# POWERMANAGE.net
KiCad netlist of a schematic drawn in Altium Designer
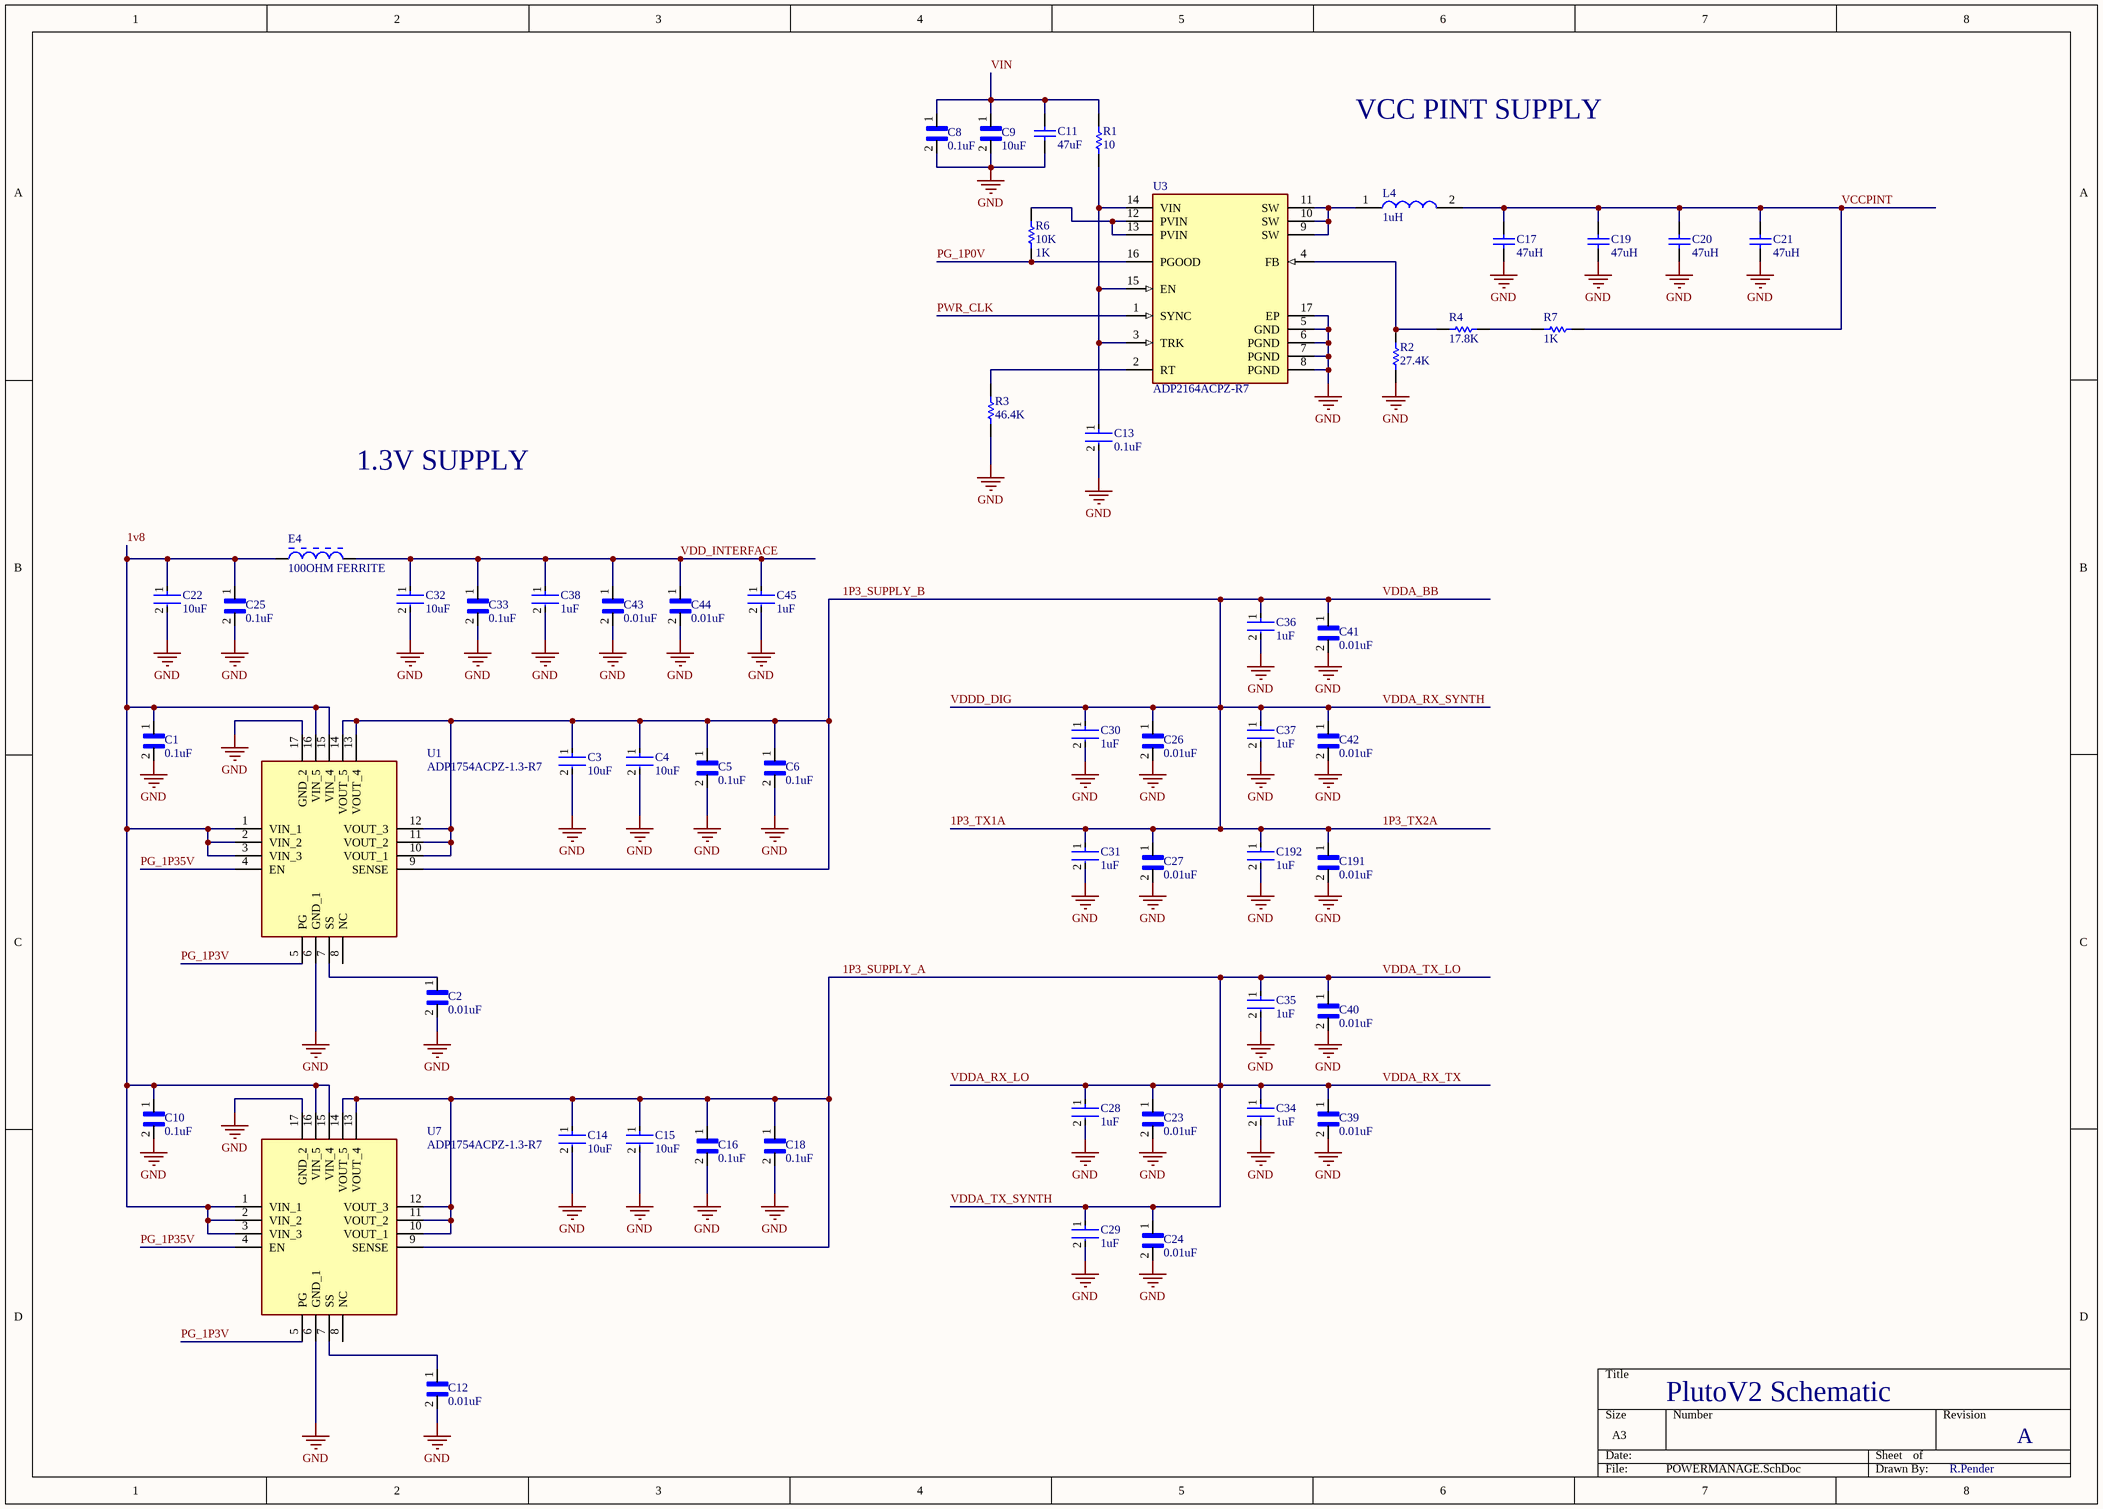
[diagram p0: POWERMANAGE.SchDoc]

(export (version "E")
  (design (tool "Eeschema 10.0.6"))
  (components
    (comp (ref "C1")
      (value "0.1uF")
      (footprint "CAPC0603X33N")
      (description "CAP 0.1UF 16VDC X5R 20% SMD 0201 PAPER TAPE")
      (fields (field (name "MP") "GRM033R61C104ME84D"))
      (libsource (lib "GRM033R61C104ME84D") (part "GRM033R61C104ME84D"))
    )
    (comp (ref "C2")
      (value "0.01uF")
      (footprint "CAPC0603X33N")
      (description "SMD Capacitor X7R(EIA) with Capacitance: 10000pF Tol. 10%. Rated Voltage: 10Vdc")
      (fields (field (name "MP") "GRM033R71A103KA01D") (field (name "MF") "Murata"))
      (libsource (lib "GRM033R71A103KA01D") (part "GRM033R71A103KA01D"))
    )
    (comp (ref "C3")
      (value "10uF")
      (footprint "FP-GRM188-0_1-e0_2_0_55-IPC_C")
      (description "Chip Multilayer Ceramic Capacitors for General Purpose, 0603, 10uF, X5R, 15%, 20%, 6.3V")
      (fields (field (name "VOLTAGE") "6.3V") (field (name "TOLERANCE") "20%"))
      (libsource (lib "Altium Content Vault") (part "02cd4be3c70576c341d710602a673aa"))
    )
    (comp (ref "C4")
      (value "10uF")
      (footprint "FP-GRM188-0_1-e0_2_0_55-IPC_C")
      (description "Chip Multilayer Ceramic Capacitors for General Purpose, 0603, 10uF, X5R, 15%, 20%, 6.3V")
      (fields (field (name "VOLTAGE") "6.3V") (field (name "TOLERANCE") "20%"))
      (libsource (lib "Altium Content Vault") (part "02cd4be3c70576c341d710602a673aa"))
    )
    (comp (ref "C5")
      (value "0.1uF")
      (footprint "CAPC0603X33N")
      (description "CAP 0.1UF 16VDC X5R 20% SMD 0201 PAPER TAPE")
      (fields (field (name "MP") "GRM033R61C104ME84D"))
      (libsource (lib "GRM033R61C104ME84D") (part "GRM033R61C104ME84D"))
    )
    (comp (ref "C6")
      (value "0.1uF")
      (footprint "CAPC0603X33N")
      (description "CAP 0.1UF 16VDC X5R 20% SMD 0201 PAPER TAPE")
      (fields (field (name "MP") "GRM033R61C104ME84D"))
      (libsource (lib "GRM033R61C104ME84D") (part "GRM033R61C104ME84D"))
    )
    (comp (ref "C8")
      (value "0.1uF")
      (footprint "CAPC0603X33N")
      (description "CAP 0.1UF 16VDC X5R 20% SMD 0201 PAPER TAPE")
      (fields (field (name "MP") "GRM033R61C104ME84D"))
      (libsource (lib "GRM033R61C104ME84D") (part "GRM033R61C104ME84D"))
    )
    (comp (ref "C9")
      (value "10uF")
      (footprint "CAPC0603X33N")
      (description "SMD Capacitor X7R(EIA) with Capacitance: 10000pF Tol. 10%. Rated Voltage: 10Vdc")
      (fields (field (name "MP") "GRM033R71A103KA01D") (field (name "MF") "Murata"))
      (libsource (lib "GRM033R71A103KA01D") (part "GRM033R71A103KA01D"))
    )
    (comp (ref "C10")
      (value "0.1uF")
      (footprint "CAPC0603X33N")
      (description "CAP 0.1UF 16VDC X5R 20% SMD 0201 PAPER TAPE")
      (fields (field (name "MP") "GRM033R61C104ME84D"))
      (libsource (lib "GRM033R61C104ME84D") (part "GRM033R61C104ME84D"))
    )
    (comp (ref "C11")
      (value "47uF")
      (footprint "TAYO-JMK212BBJ476MG-T_L")
      (fields
        (field (name "MANUFACTURER") "Taiyo Yuden")
        (field (name "TOLERANCE") "±20%")
        (field (name "PCN PART NUMBER") "X5R,X7RDielectrics23/Jan/2008")
      )
      (libsource (lib "Altium Content Vault") (part "CAP-NP-2"))
    )
    (comp (ref "C12")
      (value "0.01uF")
      (footprint "CAPC0603X33N")
      (description "SMD Capacitor X7R(EIA) with Capacitance: 10000pF Tol. 10%. Rated Voltage: 10Vdc")
      (fields (field (name "MP") "GRM033R71A103KA01D") (field (name "MF") "Murata"))
      (libsource (lib "GRM033R71A103KA01D") (part "GRM033R71A103KA01D"))
    )
    (comp (ref "C13")
      (value "0.1uF")
      (footprint "FP-GRM188-0_15-MFG")
      (description "Chip Multilayer Ceramic Capacitors for General Purpose, 0603, 10uF, X5R, 15%, 20%, 10V")
      (fields (field (name "TOLERANCE") "20%"))
      (libsource (lib "Altium Content Vault") (part "02cd4be3c70576c341d710602a673aa"))
    )
    (comp (ref "C14")
      (value "10uF")
      (footprint "FP-GRM188-0_1-e0_2_0_55-IPC_C")
      (description "Chip Multilayer Ceramic Capacitors for General Purpose, 0603, 10uF, X5R, 15%, 20%, 6.3V")
      (fields (field (name "VOLTAGE") "6.3V") (field (name "TOLERANCE") "20%"))
      (libsource (lib "Altium Content Vault") (part "02cd4be3c70576c341d710602a673aa"))
    )
    (comp (ref "C15")
      (value "10uF")
      (footprint "FP-GRM188-0_1-e0_2_0_55-IPC_C")
      (description "Chip Multilayer Ceramic Capacitors for General Purpose, 0603, 10uF, X5R, 15%, 20%, 6.3V")
      (fields (field (name "VOLTAGE") "6.3V") (field (name "TOLERANCE") "20%"))
      (libsource (lib "Altium Content Vault") (part "02cd4be3c70576c341d710602a673aa"))
    )
    (comp (ref "C16")
      (value "0.1uF")
      (footprint "CAPC0603X33N")
      (description "CAP 0.1UF 16VDC X5R 20% SMD 0201 PAPER TAPE")
      (fields (field (name "MP") "GRM033R61C104ME84D"))
      (libsource (lib "GRM033R61C104ME84D") (part "GRM033R61C104ME84D"))
    )
    (comp (ref "C17")
      (value "47uH")
      (footprint "TAYO-JMK212BBJ476MG-T_L")
      (fields
        (field (name "MANUFACTURER") "Taiyo Yuden")
        (field (name "TOLERANCE") "±20%")
        (field (name "PCN PART NUMBER") "X5R,X7RDielectrics23/Jan/2008")
      )
      (libsource (lib "Altium Content Vault") (part "CAP-NP-2"))
    )
    (comp (ref "C18")
      (value "0.1uF")
      (footprint "CAPC0603X33N")
      (description "CAP 0.1UF 16VDC X5R 20% SMD 0201 PAPER TAPE")
      (fields (field (name "MP") "GRM033R61C104ME84D"))
      (libsource (lib "GRM033R61C104ME84D") (part "GRM033R61C104ME84D"))
    )
    (comp (ref "C19")
      (value "47uH")
      (footprint "TAYO-JMK212BBJ476MG-T_L")
      (fields
        (field (name "MANUFACTURER") "Taiyo Yuden")
        (field (name "TOLERANCE") "±20%")
        (field (name "PCN PART NUMBER") "X5R,X7RDielectrics23/Jan/2008")
      )
      (libsource (lib "Altium Content Vault") (part "CAP-NP-2"))
    )
    (comp (ref "C20")
      (value "47uH")
      (footprint "TAYO-JMK212BBJ476MG-T_L")
      (fields
        (field (name "MANUFACTURER") "Taiyo Yuden")
        (field (name "TOLERANCE") "±20%")
        (field (name "PCN PART NUMBER") "X5R,X7RDielectrics23/Jan/2008")
      )
      (libsource (lib "Altium Content Vault") (part "CAP-NP-2"))
    )
    (comp (ref "C21")
      (value "47uH")
      (footprint "TAYO-JMK212BBJ476MG-T_L")
      (fields
        (field (name "MANUFACTURER") "Taiyo Yuden")
        (field (name "TOLERANCE") "±20%")
        (field (name "PCN PART NUMBER") "X5R,X7RDielectrics23/Jan/2008")
      )
      (libsource (lib "Altium Content Vault") (part "CAP-NP-2"))
    )
    (comp (ref "C22")
      (value "10uF")
      (footprint "FP-GRM188-0_1-e0_2_0_55-IPC_C")
      (description "Chip Multilayer Ceramic Capacitors for General Purpose, 0603, 10uF, X5R, 15%, 20%, 6.3V")
      (fields (field (name "VOLTAGE") "6.3V") (field (name "TOLERANCE") "20%"))
      (libsource (lib "Altium Content Vault") (part "02cd4be3c70576c341d710602a673aa"))
    )
    (comp (ref "C23")
      (value "0.01uF")
      (footprint "CAPC0603X33N")
      (description "SMD Capacitor X7R(EIA) with Capacitance: 10000pF Tol. 10%. Rated Voltage: 10Vdc")
      (fields (field (name "MP") "GRM033R71A103KA01D") (field (name "MF") "Murata"))
      (libsource (lib "GRM033R71A103KA01D") (part "GRM033R71A103KA01D"))
    )
    (comp (ref "C24")
      (value "0.01uF")
      (footprint "CAPC0603X33N")
      (description "SMD Capacitor X7R(EIA) with Capacitance: 10000pF Tol. 10%. Rated Voltage: 10Vdc")
      (fields (field (name "MP") "GRM033R71A103KA01D") (field (name "MF") "Murata"))
      (libsource (lib "GRM033R71A103KA01D") (part "GRM033R71A103KA01D"))
    )
    (comp (ref "C25")
      (value "0.1uF")
      (footprint "CAPC0603X33N")
      (description "CAP 0.1UF 16VDC X5R 20% SMD 0201 PAPER TAPE")
      (fields (field (name "MP") "GRM033R61C104ME84D"))
      (libsource (lib "GRM033R61C104ME84D") (part "GRM033R61C104ME84D"))
    )
    (comp (ref "C26")
      (value "0.01uF")
      (footprint "CAPC0603X33N")
      (description "SMD Capacitor X7R(EIA) with Capacitance: 10000pF Tol. 10%. Rated Voltage: 10Vdc")
      (fields (field (name "MP") "GRM033R71A103KA01D") (field (name "MF") "Murata"))
      (libsource (lib "GRM033R71A103KA01D") (part "GRM033R71A103KA01D"))
    )
    (comp (ref "C27")
      (value "0.01uF")
      (footprint "CAPC0603X33N")
      (description "SMD Capacitor X7R(EIA) with Capacitance: 10000pF Tol. 10%. Rated Voltage: 10Vdc")
      (fields (field (name "MP") "GRM033R71A103KA01D") (field (name "MF") "Murata"))
      (libsource (lib "GRM033R71A103KA01D") (part "GRM033R71A103KA01D"))
    )
    (comp (ref "C28")
      (value "1uF")
      (footprint "FP-0402-L_1_0_0_05-W_0_5-IPC_B")
      (description "None")
      (fields (field (name "TOLERANCE") "10%"))
      (libsource (lib "Altium Content Vault") (part "b4654b650e69147ec39a6b967a45e02"))
    )
    (comp (ref "C29")
      (value "1uF")
      (footprint "FP-0402-L_1_0_0_05-W_0_5-IPC_B")
      (description "None")
      (fields (field (name "TOLERANCE") "10%"))
      (libsource (lib "Altium Content Vault") (part "b4654b650e69147ec39a6b967a45e02"))
    )
    (comp (ref "C30")
      (value "1uF")
      (footprint "FP-0402-L_1_0_0_05-W_0_5-IPC_B")
      (description "None")
      (fields (field (name "TOLERANCE") "10%"))
      (libsource (lib "Altium Content Vault") (part "b4654b650e69147ec39a6b967a45e02"))
    )
    (comp (ref "C31")
      (value "1uF")
      (footprint "FP-0402-L_1_0_0_05-W_0_5-IPC_B")
      (description "None")
      (fields (field (name "TOLERANCE") "10%"))
      (libsource (lib "Altium Content Vault") (part "b4654b650e69147ec39a6b967a45e02"))
    )
    (comp (ref "C32")
      (value "10uF")
      (footprint "FP-GRM188-0_1-e0_2_0_55-IPC_C")
      (description "Chip Multilayer Ceramic Capacitors for General Purpose, 0603, 10uF, X5R, 15%, 20%, 6.3V")
      (fields (field (name "VOLTAGE") "6.3V") (field (name "TOLERANCE") "20%"))
      (libsource (lib "Altium Content Vault") (part "02cd4be3c70576c341d710602a673aa"))
    )
    (comp (ref "C33")
      (value "0.1uF")
      (footprint "CAPC0603X33N")
      (description "CAP 0.1UF 16VDC X5R 20% SMD 0201 PAPER TAPE")
      (fields (field (name "MP") "GRM033R61C104ME84D"))
      (libsource (lib "GRM033R61C104ME84D") (part "GRM033R61C104ME84D"))
    )
    (comp (ref "C34")
      (value "1uF")
      (footprint "FP-0402-L_1_0_0_05-W_0_5-IPC_B")
      (description "None")
      (fields (field (name "TOLERANCE") "10%"))
      (libsource (lib "Altium Content Vault") (part "b4654b650e69147ec39a6b967a45e02"))
    )
    (comp (ref "C35")
      (value "1uF")
      (footprint "FP-0402-L_1_0_0_05-W_0_5-IPC_B")
      (description "None")
      (fields (field (name "TOLERANCE") "10%"))
      (libsource (lib "Altium Content Vault") (part "b4654b650e69147ec39a6b967a45e02"))
    )
    (comp (ref "C36")
      (value "1uF")
      (footprint "FP-0402-L_1_0_0_05-W_0_5-IPC_B")
      (description "None")
      (fields (field (name "TOLERANCE") "10%"))
      (libsource (lib "Altium Content Vault") (part "b4654b650e69147ec39a6b967a45e02"))
    )
    (comp (ref "C37")
      (value "1uF")
      (footprint "FP-0402-L_1_0_0_05-W_0_5-IPC_B")
      (description "None")
      (fields (field (name "TOLERANCE") "10%"))
      (libsource (lib "Altium Content Vault") (part "b4654b650e69147ec39a6b967a45e02"))
    )
    (comp (ref "C38")
      (value "1uF")
      (footprint "FP-0402-L_1_0_0_05-W_0_5-IPC_A")
      (description "None")
      (fields (field (name "TOLERANCE") "10%"))
      (libsource (lib "Altium Content Vault") (part "b4654b650e69147ec39a6b967a45e02"))
    )
    (comp (ref "C39")
      (value "0.01uF")
      (footprint "CAPC0603X33N")
      (description "SMD Capacitor X7R(EIA) with Capacitance: 10000pF Tol. 10%. Rated Voltage: 10Vdc")
      (fields (field (name "MP") "GRM033R71A103KA01D") (field (name "MF") "Murata"))
      (libsource (lib "GRM033R71A103KA01D") (part "GRM033R71A103KA01D"))
    )
    (comp (ref "C40")
      (value "0.01uF")
      (footprint "CAPC0603X33N")
      (description "SMD Capacitor X7R(EIA) with Capacitance: 10000pF Tol. 10%. Rated Voltage: 10Vdc")
      (fields (field (name "MP") "GRM033R71A103KA01D") (field (name "MF") "Murata"))
      (libsource (lib "GRM033R71A103KA01D") (part "GRM033R71A103KA01D"))
    )
    (comp (ref "C41")
      (value "0.01uF")
      (footprint "CAPC0603X33N")
      (description "SMD Capacitor X7R(EIA) with Capacitance: 10000pF Tol. 10%. Rated Voltage: 10Vdc")
      (fields (field (name "MP") "GRM033R71A103KA01D") (field (name "MF") "Murata"))
      (libsource (lib "GRM033R71A103KA01D") (part "GRM033R71A103KA01D"))
    )
    (comp (ref "C42")
      (value "0.01uF")
      (footprint "CAPC0603X33N")
      (description "SMD Capacitor X7R(EIA) with Capacitance: 10000pF Tol. 10%. Rated Voltage: 10Vdc")
      (fields (field (name "MP") "GRM033R71A103KA01D") (field (name "MF") "Murata"))
      (libsource (lib "GRM033R71A103KA01D") (part "GRM033R71A103KA01D"))
    )
    (comp (ref "C43")
      (value "0.01uF")
      (footprint "CAPC0603X33N")
      (description "SMD Capacitor X7R(EIA) with Capacitance: 10000pF Tol. 10%. Rated Voltage: 10Vdc")
      (fields (field (name "MP") "GRM033R71A103KA01D") (field (name "MF") "Murata"))
      (libsource (lib "GRM033R71A103KA01D") (part "GRM033R71A103KA01D"))
    )
    (comp (ref "C44")
      (value "0.01uF")
      (footprint "CAPC0603X33N")
      (description "SMD Capacitor X7R(EIA) with Capacitance: 10000pF Tol. 10%. Rated Voltage: 10Vdc")
      (fields (field (name "MP") "GRM033R71A103KA01D") (field (name "MF") "Murata"))
      (libsource (lib "GRM033R71A103KA01D") (part "GRM033R71A103KA01D"))
    )
    (comp (ref "C45")
      (value "1uF")
      (footprint "FP-0402-L_1_0_0_05-W_0_5-IPC_A")
      (description "None")
      (fields (field (name "TOLERANCE") "10%"))
      (libsource (lib "Altium Content Vault") (part "b4654b650e69147ec39a6b967a45e02"))
    )
    (comp (ref "C191")
      (value "0.01uF")
      (footprint "CAPC0603X33N")
      (description "SMD Capacitor X7R(EIA) with Capacitance: 10000pF Tol. 10%. Rated Voltage: 10Vdc")
      (fields (field (name "MP") "GRM033R71A103KA01D") (field (name "MF") "Murata"))
      (libsource (lib "GRM033R71A103KA01D") (part "GRM033R71A103KA01D"))
    )
    (comp (ref "C192")
      (value "1uF")
      (footprint "FP-0402-L_1_0_0_05-W_0_5-IPC_B")
      (description "None")
      (fields (field (name "TOLERANCE") "10%"))
      (libsource (lib "Altium Content Vault") (part "b4654b650e69147ec39a6b967a45e02"))
    )
    (comp (ref "E4")
      (value "100OHM FERRITE")
      (footprint "TDK-MPZ2012S101A-2_V")
      (fields (field (name "TOLERANCE") "25%") (field (name "MANUFACTURER") "TDK"))
      (libsource (lib "Altium Content Vault") (part "BEAD-2"))
    )
    (comp (ref "L4")
      (value "1uH")
      (footprint "SamacSys:XFL4020102MEB")
      (description "Inductor")
      (fields (field (name "MANUFACTURER_PART_NUMBER") "XFL4020-102MEB"))
      (libsource (lib "*") (part "XFL4020-102MEB"))
    )
    (comp (ref "R1")
      (value "10")
      (footprint "RESC0603X26X15LL03T05")
      (fields (field (name "MANUFACTURER") "Panasonic") (field (name "PART NUMBER") "ERJ1GNF10R0C"))
      (libsource (lib "Altium Content Vault") (part "RES"))
    )
    (comp (ref "R2")
      (value "27.4K")
      (footprint "2-0402")
      (fields (field (name "PUBLISHER") "Altium Limited"))
      (libsource (lib "Panasonic Resistor") (part "ERJ2RK"))
    )
    (comp (ref "R3")
      (value "46.4K")
      (footprint "1-0201")
      (description "Thick Film Chip Resistor, 10 Ohm to 1M Ohm Range, 5% Tolerance, 0201 Size, 0.05 W")
      (fields (field (name "PUBLISHER") "Altium Limited"))
      (libsource (lib "Panasonic Resistor") (part "ERJ1GE"))
    )
    (comp (ref "R4")
      (value "17.8K")
      (footprint "2-0402")
      (fields (field (name "PUBLISHER") "Altium Limited"))
      (libsource (lib "Panasonic Resistor") (part "ERJ2RK"))
    )
    (comp (ref "R6")
      (value "10K")
      (footprint "RESC1005X35N")
      (description "Resistor")
      (fields (field (name "ALTIUM_VALUE") "1K") (field (name "PUBLISHER") "Altium Limited"))
      (libsource (lib "Miscellaneous Devices") (part "Res1"))
    )
    (comp (ref "R7")
      (value "1K")
      (footprint "2-0402")
      (fields (field (name "PUBLISHER") "Altium Limited"))
      (libsource (lib "Panasonic Resistor") (part "ERJ2RK"))
    )
    (comp (ref "U1")
      (value "ADP1754ACPZ-1.3-R7")
      (footprint "SamacSys:QFN65P400X400X80-17N-D")
      (description "Integrated Circuit")
      (libsource (lib "*") (part "ADP1754ACPZ-1.3-R7"))
    )
    (comp (ref "U3")
      (value "ADP2164ACPZ-R7")
      (footprint "FP-CP-16-26-IPC_C")
      (description "Buck Switching Regulator IC Positive Adjustable 0.6V 1 Output 4A 16-WQFN Exposed Pad, CSP")
      (fields (field (name "MANUFACTURER") "Analog Devices"))
      (libsource (lib "Altium Content Vault") (part "77e3d03b05ecb97249e3a8385dd6fb0"))
    )
    (comp (ref "U7")
      (value "ADP1754ACPZ-1.3-R7")
      (footprint "SamacSys:QFN65P400X400X80-17N-D")
      (description "Integrated Circuit")
      (libsource (lib "*") (part "ADP1754ACPZ-1.3-R7"))
    )
  )
  (nets
    (net (code "1") (name "/1P3_SUPPLY_A") (class "Default")
      (node (ref "C14") (pin "1") (pinfunction "1_1") (pintype "passive"))
      (node (ref "C15") (pin "1") (pinfunction "1_1") (pintype "passive"))
      (node (ref "C16") (pin "1") (pinfunction "1_1") (pintype "passive"))
      (node (ref "C18") (pin "1") (pinfunction "1_1") (pintype "passive"))
      (node (ref "C23") (pin "1") (pinfunction "1_1") (pintype "passive"))
      (node (ref "C24") (pin "1") (pinfunction "1_1") (pintype "passive"))
      (node (ref "C28") (pin "1") (pinfunction "1_1") (pintype "passive"))
      (node (ref "C29") (pin "1") (pinfunction "1_1") (pintype "passive"))
      (node (ref "C34") (pin "1") (pinfunction "1_1") (pintype "passive"))
      (node (ref "C35") (pin "1") (pinfunction "1_1") (pintype "passive"))
      (node (ref "C39") (pin "1") (pinfunction "1_1") (pintype "passive"))
      (node (ref "C40") (pin "1") (pinfunction "1_1") (pintype "passive"))
      (node (ref "U7") (pin "10") (pinfunction "VOUT_1_10") (pintype "passive"))
      (node (ref "U7") (pin "11") (pinfunction "VOUT_2_11") (pintype "passive"))
      (node (ref "U7") (pin "12") (pinfunction "VOUT_3_12") (pintype "passive"))
      (node (ref "U7") (pin "13") (pinfunction "VOUT_4_13") (pintype "passive"))
      (node (ref "U7") (pin "14") (pinfunction "VOUT_5_14") (pintype "passive"))
      (node (ref "U7") (pin "9") (pinfunction "SENSE_9") (pintype "passive"))
    )
    (net (code "2") (name "/1P3_SUPPLY_B") (class "Default")
      (node (ref "C191") (pin "1") (pinfunction "1_1") (pintype "passive"))
      (node (ref "C192") (pin "1") (pinfunction "1_1") (pintype "passive"))
      (node (ref "C26") (pin "1") (pinfunction "1_1") (pintype "passive"))
      (node (ref "C27") (pin "1") (pinfunction "1_1") (pintype "passive"))
      (node (ref "C3") (pin "1") (pinfunction "1_1") (pintype "passive"))
      (node (ref "C30") (pin "1") (pinfunction "1_1") (pintype "passive"))
      (node (ref "C31") (pin "1") (pinfunction "1_1") (pintype "passive"))
      (node (ref "C36") (pin "1") (pinfunction "1_1") (pintype "passive"))
      (node (ref "C37") (pin "1") (pinfunction "1_1") (pintype "passive"))
      (node (ref "C4") (pin "1") (pinfunction "1_1") (pintype "passive"))
      (node (ref "C41") (pin "1") (pinfunction "1_1") (pintype "passive"))
      (node (ref "C42") (pin "1") (pinfunction "1_1") (pintype "passive"))
      (node (ref "C5") (pin "1") (pinfunction "1_1") (pintype "passive"))
      (node (ref "C6") (pin "1") (pinfunction "1_1") (pintype "passive"))
      (node (ref "U1") (pin "10") (pinfunction "VOUT_1_10") (pintype "passive"))
      (node (ref "U1") (pin "11") (pinfunction "VOUT_2_11") (pintype "passive"))
      (node (ref "U1") (pin "12") (pinfunction "VOUT_3_12") (pintype "passive"))
      (node (ref "U1") (pin "13") (pinfunction "VOUT_4_13") (pintype "passive"))
      (node (ref "U1") (pin "14") (pinfunction "VOUT_5_14") (pintype "passive"))
      (node (ref "U1") (pin "9") (pinfunction "SENSE_9") (pintype "passive"))
    )
    (net (code "3") (name "/1v8") (class "Default")
      (node (ref "C1") (pin "1") (pinfunction "1_1") (pintype "passive"))
      (node (ref "C10") (pin "1") (pinfunction "1_1") (pintype "passive"))
      (node (ref "C22") (pin "1") (pinfunction "1_1") (pintype "passive"))
      (node (ref "C25") (pin "1") (pinfunction "1_1") (pintype "passive"))
      (node (ref "E4") (pin "1") (pinfunction "1_1") (pintype "passive"))
      (node (ref "U1") (pin "1") (pinfunction "VIN_1_1") (pintype "passive"))
      (node (ref "U1") (pin "15") (pinfunction "VIN_4_15") (pintype "passive"))
      (node (ref "U1") (pin "16") (pinfunction "VIN_5_16") (pintype "passive"))
      (node (ref "U1") (pin "2") (pinfunction "VIN_2_2") (pintype "passive"))
      (node (ref "U1") (pin "3") (pinfunction "VIN_3_3") (pintype "passive"))
      (node (ref "U7") (pin "1") (pinfunction "VIN_1_1") (pintype "passive"))
      (node (ref "U7") (pin "15") (pinfunction "VIN_4_15") (pintype "passive"))
      (node (ref "U7") (pin "16") (pinfunction "VIN_5_16") (pintype "passive"))
      (node (ref "U7") (pin "2") (pinfunction "VIN_2_2") (pintype "passive"))
      (node (ref "U7") (pin "3") (pinfunction "VIN_3_3") (pintype "passive"))
    )
    (net (code "4") (name "/PG_1P0V") (class "Default")
      (node (ref "R6") (pin "1") (pinfunction "1_1") (pintype "passive"))
      (node (ref "U3") (pin "16") (pinfunction "PGOOD_16") (pintype "open_collector"))
    )
    (net (code "5") (name "/PG_1P3V") (class "Default")
      (node (ref "U1") (pin "5") (pinfunction "PG_5") (pintype "passive"))
      (node (ref "U7") (pin "5") (pinfunction "PG_5") (pintype "passive"))
    )
    (net (code "6") (name "/PG_1P35V") (class "Default")
      (node (ref "U1") (pin "4") (pinfunction "EN_4") (pintype "passive"))
      (node (ref "U7") (pin "4") (pinfunction "EN_4") (pintype "passive"))
    )
    (net (code "7") (name "/PWR_CLK") (class "Default")
      (node (ref "U3") (pin "1") (pinfunction "SYNC_1") (pintype "input"))
    )
    (net (code "8") (name "/VCCPINT") (class "Default")
      (node (ref "C17") (pin "1") (pinfunction "1_1") (pintype "passive"))
      (node (ref "C19") (pin "1") (pinfunction "1_1") (pintype "passive"))
      (node (ref "C20") (pin "1") (pinfunction "1_1") (pintype "passive"))
      (node (ref "C21") (pin "1") (pinfunction "1_1") (pintype "passive"))
      (node (ref "L4") (pin "2") (pinfunction "2_2") (pintype "passive"))
      (node (ref "R7") (pin "2") (pinfunction "2_2") (pintype "passive"))
    )
    (net (code "9") (name "/VDD_INTERFACE") (class "Default")
      (node (ref "C32") (pin "1") (pinfunction "1_1") (pintype "passive"))
      (node (ref "C33") (pin "1") (pinfunction "1_1") (pintype "passive"))
      (node (ref "C38") (pin "1") (pinfunction "1_1") (pintype "passive"))
      (node (ref "C43") (pin "1") (pinfunction "1_1") (pintype "passive"))
      (node (ref "C44") (pin "1") (pinfunction "1_1") (pintype "passive"))
      (node (ref "C45") (pin "1") (pinfunction "1_1") (pintype "passive"))
      (node (ref "E4") (pin "2") (pinfunction "2_2") (pintype "passive"))
    )
    (net (code "10") (name "/VIN") (class "Default")
      (node (ref "C11") (pin "1") (pinfunction "1_1") (pintype "passive"))
      (node (ref "C8") (pin "1") (pinfunction "1_1") (pintype "passive"))
      (node (ref "C9") (pin "1") (pinfunction "1_1") (pintype "passive"))
      (node (ref "R1") (pin "2") (pinfunction "2_2") (pintype "passive"))
    )
    (net (code "11") (name "GND") (class "Default")
      (node (ref "C1") (pin "2") (pinfunction "2_2") (pintype "passive"))
      (node (ref "C10") (pin "2") (pinfunction "2_2") (pintype "passive"))
      (node (ref "C11") (pin "2") (pinfunction "2_2") (pintype "passive"))
      (node (ref "C12") (pin "2") (pinfunction "2_2") (pintype "passive"))
      (node (ref "C13") (pin "2") (pinfunction "2_2") (pintype "passive"))
      (node (ref "C14") (pin "2") (pinfunction "2_2") (pintype "passive"))
      (node (ref "C15") (pin "2") (pinfunction "2_2") (pintype "passive"))
      (node (ref "C16") (pin "2") (pinfunction "2_2") (pintype "passive"))
      (node (ref "C17") (pin "2") (pinfunction "2_2") (pintype "passive"))
      (node (ref "C18") (pin "2") (pinfunction "2_2") (pintype "passive"))
      (node (ref "C19") (pin "2") (pinfunction "2_2") (pintype "passive"))
      (node (ref "C191") (pin "2") (pinfunction "2_2") (pintype "passive"))
      (node (ref "C192") (pin "2") (pinfunction "2_2") (pintype "passive"))
      (node (ref "C2") (pin "2") (pinfunction "2_2") (pintype "passive"))
      (node (ref "C20") (pin "2") (pinfunction "2_2") (pintype "passive"))
      (node (ref "C21") (pin "2") (pinfunction "2_2") (pintype "passive"))
      (node (ref "C22") (pin "2") (pinfunction "2_2") (pintype "passive"))
      (node (ref "C23") (pin "2") (pinfunction "2_2") (pintype "passive"))
      (node (ref "C24") (pin "2") (pinfunction "2_2") (pintype "passive"))
      (node (ref "C25") (pin "2") (pinfunction "2_2") (pintype "passive"))
      (node (ref "C26") (pin "2") (pinfunction "2_2") (pintype "passive"))
      (node (ref "C27") (pin "2") (pinfunction "2_2") (pintype "passive"))
      (node (ref "C28") (pin "2") (pinfunction "2_2") (pintype "passive"))
      (node (ref "C29") (pin "2") (pinfunction "2_2") (pintype "passive"))
      (node (ref "C3") (pin "2") (pinfunction "2_2") (pintype "passive"))
      (node (ref "C30") (pin "2") (pinfunction "2_2") (pintype "passive"))
      (node (ref "C31") (pin "2") (pinfunction "2_2") (pintype "passive"))
      (node (ref "C32") (pin "2") (pinfunction "2_2") (pintype "passive"))
      (node (ref "C33") (pin "2") (pinfunction "2_2") (pintype "passive"))
      (node (ref "C34") (pin "2") (pinfunction "2_2") (pintype "passive"))
      (node (ref "C35") (pin "2") (pinfunction "2_2") (pintype "passive"))
      (node (ref "C36") (pin "2") (pinfunction "2_2") (pintype "passive"))
      (node (ref "C37") (pin "2") (pinfunction "2_2") (pintype "passive"))
      (node (ref "C38") (pin "2") (pinfunction "2_2") (pintype "passive"))
      (node (ref "C39") (pin "2") (pinfunction "2_2") (pintype "passive"))
      (node (ref "C4") (pin "2") (pinfunction "2_2") (pintype "passive"))
      (node (ref "C40") (pin "2") (pinfunction "2_2") (pintype "passive"))
      (node (ref "C41") (pin "2") (pinfunction "2_2") (pintype "passive"))
      (node (ref "C42") (pin "2") (pinfunction "2_2") (pintype "passive"))
      (node (ref "C43") (pin "2") (pinfunction "2_2") (pintype "passive"))
      (node (ref "C44") (pin "2") (pinfunction "2_2") (pintype "passive"))
      (node (ref "C45") (pin "2") (pinfunction "2_2") (pintype "passive"))
      (node (ref "C5") (pin "2") (pinfunction "2_2") (pintype "passive"))
      (node (ref "C6") (pin "2") (pinfunction "2_2") (pintype "passive"))
      (node (ref "C8") (pin "2") (pinfunction "2_2") (pintype "passive"))
      (node (ref "C9") (pin "2") (pinfunction "2_2") (pintype "passive"))
      (node (ref "R2") (pin "2") (pinfunction "2_2") (pintype "passive"))
      (node (ref "R3") (pin "2") (pinfunction "2_2") (pintype "passive"))
      (node (ref "U1") (pin "17") (pinfunction "GND_2_17") (pintype "passive"))
      (node (ref "U1") (pin "6") (pinfunction "GND_1_6") (pintype "passive"))
      (node (ref "U3") (pin "17") (pinfunction "EP_17") (pintype "power_in"))
      (node (ref "U3") (pin "5") (pinfunction "GND_5") (pintype "power_in"))
      (node (ref "U3") (pin "6") (pinfunction "PGND_6") (pintype "power_in"))
      (node (ref "U3") (pin "7") (pinfunction "PGND_7") (pintype "power_in"))
      (node (ref "U3") (pin "8") (pinfunction "PGND_8") (pintype "power_in"))
      (node (ref "U7") (pin "17") (pinfunction "GND_2_17") (pintype "passive"))
      (node (ref "U7") (pin "6") (pinfunction "GND_1_6") (pintype "passive"))
    )
    (net (code "12") (name "Net-(L4-Pad1)") (class "Default")
      (node (ref "L4") (pin "1") (pinfunction "1_1") (pintype "passive"))
      (node (ref "U3") (pin "10") (pinfunction "SW_10") (pintype "power_in"))
      (node (ref "U3") (pin "11") (pinfunction "SW_11") (pintype "power_in"))
      (node (ref "U3") (pin "9") (pinfunction "SW_9") (pintype "power_in"))
    )
    (net (code "13") (name "Net-(R4-Pad2)") (class "Default")
      (node (ref "R4") (pin "2") (pinfunction "2_2") (pintype "passive"))
      (node (ref "R7") (pin "1") (pinfunction "1_1") (pintype "passive"))
    )
    (net (code "14") (name "Net-(R6-Pad2)") (class "Default")
      (node (ref "R6") (pin "2") (pinfunction "2_2") (pintype "passive"))
      (node (ref "U3") (pin "12") (pinfunction "PVIN_12") (pintype "power_in"))
      (node (ref "U3") (pin "13") (pinfunction "PVIN_13") (pintype "power_in"))
    )
    (net (code "15") (name "Net-(U1-SS)") (class "Default")
      (node (ref "C2") (pin "1") (pinfunction "1_1") (pintype "passive"))
      (node (ref "U1") (pin "7") (pinfunction "SS_7") (pintype "passive"))
    )
    (net (code "16") (name "Net-(U3-EN)") (class "Default")
      (node (ref "C13") (pin "1") (pinfunction "1_1") (pintype "passive"))
      (node (ref "R1") (pin "1") (pinfunction "1_1") (pintype "passive"))
      (node (ref "U3") (pin "14") (pinfunction "VIN_14") (pintype "power_in"))
      (node (ref "U3") (pin "15") (pinfunction "EN_15") (pintype "input"))
      (node (ref "U3") (pin "3") (pinfunction "TRK_3") (pintype "input"))
    )
    (net (code "17") (name "Net-(U3-FB)") (class "Default")
      (node (ref "R2") (pin "1") (pinfunction "1_1") (pintype "passive"))
      (node (ref "R4") (pin "1") (pinfunction "1_1") (pintype "passive"))
      (node (ref "U3") (pin "4") (pinfunction "FB_4") (pintype "input"))
    )
    (net (code "18") (name "Net-(U3-RT)") (class "Default")
      (node (ref "R3") (pin "1") (pinfunction "1_1") (pintype "passive"))
      (node (ref "U3") (pin "2") (pinfunction "RT_2") (pintype "passive"))
    )
    (net (code "19") (name "Net-(U7-SS)") (class "Default")
      (node (ref "C12") (pin "1") (pinfunction "1_1") (pintype "passive"))
      (node (ref "U7") (pin "7") (pinfunction "SS_7") (pintype "passive"))
    )
    (net (code "20") (name "unconnected-(U1-NC-Pad8)") (class "Default")
      (node (ref "U1") (pin "8") (pinfunction "NC_8") (pintype "passive"))
    )
    (net (code "21") (name "unconnected-(U7-NC-Pad8)") (class "Default")
      (node (ref "U7") (pin "8") (pinfunction "NC_8") (pintype "passive"))
    )
  )
)
